# UniversalSaftSwitch.net
KiCad netlist of a schematic drawn in EAGLE
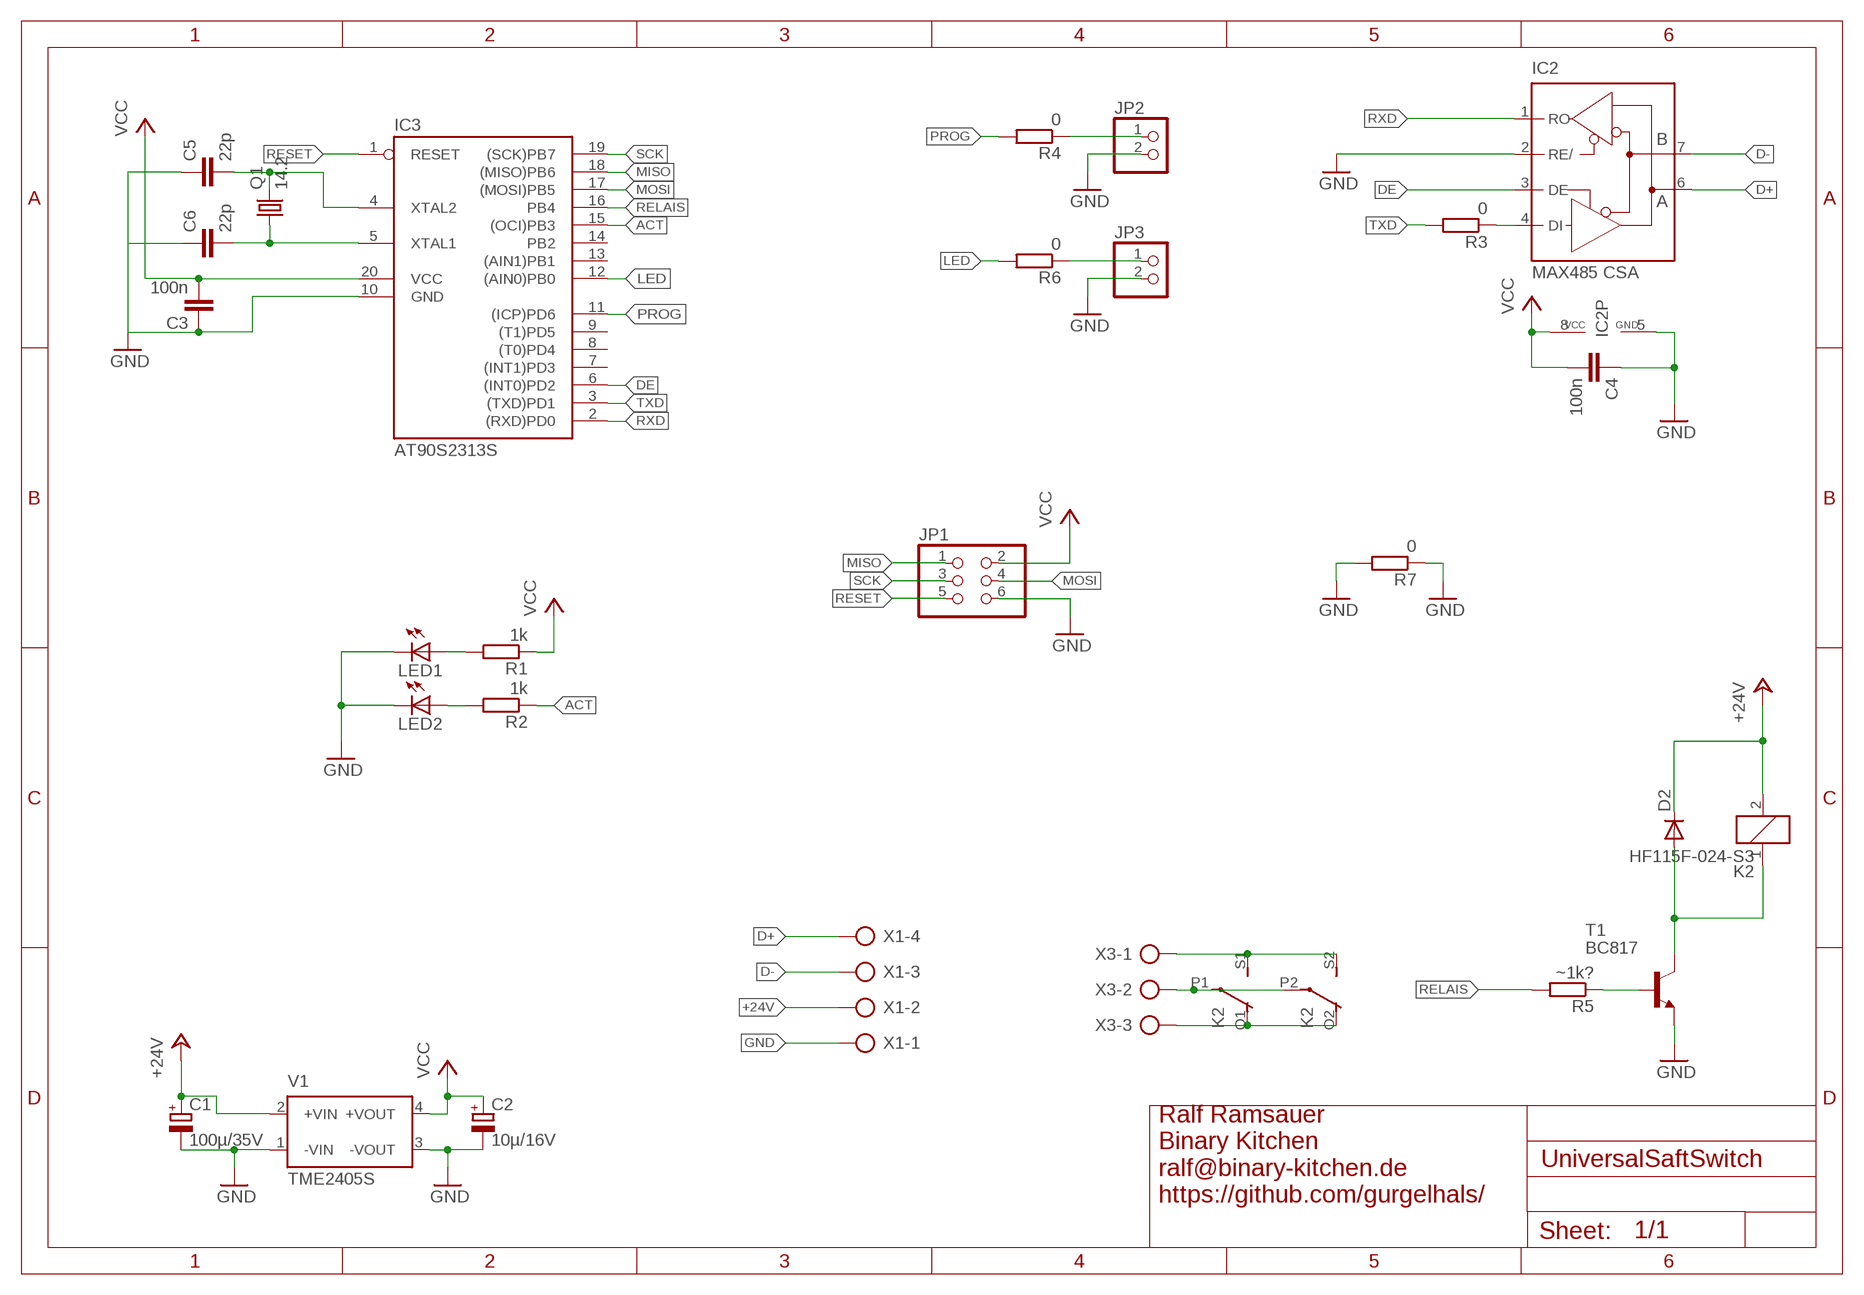
[diagram p0: schematic, sheet 1]

(export (version "E")
  (design (tool "Eeschema 10.0.6"))
  (components
    (comp (ref "C1")
      (value "100µ/35V")
      (footprint "eagle-import:E3,5-8")
      (libsource (lib "eagle-import") (part "CPOL-EUE3.5-8"))
    )
    (comp (ref "C2")
      (value "10µ/16V")
      (footprint "eagle-import:E2-4")
      (libsource (lib "eagle-import") (part "CPOL-EUE2-4"))
    )
    (comp (ref "C3")
      (value "100n")
      (footprint "eagle-import:C0805K")
      (libsource (lib "eagle-import") (part "C-EUC0805K"))
    )
    (comp (ref "C4")
      (value "100n")
      (footprint "eagle-import:C0805K")
      (libsource (lib "eagle-import") (part "C-EUC0805K"))
    )
    (comp (ref "C5")
      (value "22p")
      (footprint "eagle-import:C0805K")
      (libsource (lib "eagle-import") (part "C-EUC0805K"))
    )
    (comp (ref "C6")
      (value "22p")
      (footprint "eagle-import:C0805K")
      (libsource (lib "eagle-import") (part "C-EUC0805K"))
    )
    (comp (ref "D2")
      (value "DIODE-MINIMELF")
      (footprint "eagle-import:MINIMELF")
      (libsource (lib "eagle-import") (part "DIODE-MINIMELF"))
    )
    (comp (ref "IC2")
      (value "MAX485 CSA")
      (footprint "eagle-import:SO08")
      (libsource (lib "eagle-import") (part "MAX481CSA"))
    )
    (comp (ref "IC3")
      (value "AT90S2313S")
      (footprint "eagle-import:SO20L")
      (libsource (lib "eagle-import") (part "AT90S2313S"))
    )
    (comp (ref "JP1")
      (value "PINHD-2X3")
      (footprint "eagle-import:2X03")
      (libsource (lib "eagle-import") (part "PINHD-2X3"))
    )
    (comp (ref "JP2")
      (value "PINHD-1X2")
      (footprint "eagle-import:1X02")
      (libsource (lib "eagle-import") (part "PINHD-1X2"))
    )
    (comp (ref "JP3")
      (value "PINHD-1X2")
      (footprint "eagle-import:1X02")
      (libsource (lib "eagle-import") (part "PINHD-1X2"))
    )
    (comp (ref "K2")
      (value "HF115F-024-S3")
      (footprint "eagle-import:F4052")
      (libsource (lib "eagle-import") (part "4052"))
    )
    (comp (ref "LED1")
      (value "LED3MM")
      (footprint "eagle-import:LED3MM")
      (libsource (lib "eagle-import") (part "LED3MM"))
    )
    (comp (ref "LED2")
      (value "LED3MM")
      (footprint "eagle-import:LED3MM")
      (libsource (lib "eagle-import") (part "LED3MM"))
    )
    (comp (ref "Q1")
      (value "14.2")
      (footprint "eagle-import:HC49U-V")
      (libsource (lib "eagle-import") (part "CRYSTALHC49U-V"))
    )
    (comp (ref "R1")
      (value "1k")
      (footprint "eagle-import:M0805")
      (libsource (lib "eagle-import") (part "R-EU_M0805"))
    )
    (comp (ref "R2")
      (value "1k")
      (footprint "eagle-import:M0805")
      (libsource (lib "eagle-import") (part "R-EU_M0805"))
    )
    (comp (ref "R3")
      (value "0")
      (footprint "eagle-import:M0805")
      (libsource (lib "eagle-import") (part "R-EU_M0805"))
    )
    (comp (ref "R4")
      (value "0")
      (footprint "eagle-import:M0805")
      (libsource (lib "eagle-import") (part "R-EU_M0805"))
    )
    (comp (ref "R5")
      (value "~1k?")
      (footprint "eagle-import:M0805")
      (libsource (lib "eagle-import") (part "R-EU_M0805"))
    )
    (comp (ref "R6")
      (value "0")
      (footprint "eagle-import:M0805")
      (libsource (lib "eagle-import") (part "R-EU_M0805"))
    )
    (comp (ref "R7")
      (value "0")
      (footprint "eagle-import:M0805")
      (libsource (lib "eagle-import") (part "R-EU_M0805"))
    )
    (comp (ref "T1")
      (value "BC817")
      (footprint "eagle-import:SOT23-BEC")
      (libsource (lib "eagle-import") (part "-NPN-SOT23-BECBC817-16"))
    )
    (comp (ref "V1")
      (value "TME2405S")
      (footprint "eagle-import:TME-24V")
      (fields (field (name "MPN") "TME 2405S"))
      (libsource (lib "eagle-import") (part "TME?2405S"))
    )
    (comp (ref "X1")
      (value "AK500/4")
      (footprint "eagle-import:AK500_4")
      (libsource (lib "eagle-import") (part "AK500/4"))
    )
    (comp (ref "X3")
      (value "AK500/3")
      (footprint "eagle-import:AK500_3")
      (libsource (lib "eagle-import") (part "AK500/3"))
    )
  )
  (nets
    (net (code "1") (name "+24V") (class "Default")
      (node (ref "C1") (pin "+") (pinfunction "+_+") (pintype "passive"))
      (node (ref "D2") (pin "C") (pinfunction "C_C") (pintype "passive"))
      (node (ref "K2") (pin "2") (pinfunction "2_2") (pintype "passive"))
      (node (ref "V1") (pin "2") (pinfunction "+VIN_2") (pintype "passive"))
      (node (ref "X1") (pin "2") (pinfunction "KL_2") (pintype "passive"))
    )
    (net (code "2") (name "ACT") (class "Default")
      (node (ref "IC3") (pin "15") (pinfunction "(OCI)PB3_15") (pintype "bidirectional"))
      (node (ref "R2") (pin "1") (pinfunction "1_1") (pintype "passive"))
    )
    (net (code "3") (name "D+") (class "Default")
      (node (ref "IC2") (pin "6") (pinfunction "A_6") (pintype "passive"))
      (node (ref "X1") (pin "4") (pinfunction "KL_4") (pintype "passive"))
    )
    (net (code "4") (name "D-") (class "Default")
      (node (ref "IC2") (pin "7") (pinfunction "B_7") (pintype "passive"))
      (node (ref "X1") (pin "3") (pinfunction "KL_3") (pintype "passive"))
    )
    (net (code "5") (name "DE") (class "Default")
      (node (ref "IC2") (pin "3") (pinfunction "DE_3") (pintype "input"))
      (node (ref "IC3") (pin "6") (pinfunction "(INT0)PD2_6") (pintype "bidirectional"))
    )
    (net (code "6") (name "GND") (class "Default")
      (node (ref "C1") (pin "-") (pinfunction "-_-") (pintype "passive"))
      (node (ref "C2") (pin "-") (pinfunction "-_-") (pintype "passive"))
      (node (ref "C3") (pin "1") (pinfunction "1_1") (pintype "passive"))
      (node (ref "C4") (pin "1") (pinfunction "1_1") (pintype "passive"))
      (node (ref "C5") (pin "1") (pinfunction "1_1") (pintype "passive"))
      (node (ref "C6") (pin "1") (pinfunction "1_1") (pintype "passive"))
      (node (ref "IC2") (pin "2") (pinfunction "RE/_2") (pintype "input"))
      (node (ref "IC2") (pin "5") (pinfunction "GND_5") (pintype "power_in"))
      (node (ref "IC3") (pin "10") (pinfunction "GND_10") (pintype "power_in"))
      (node (ref "JP1") (pin "6") (pinfunction "6_6") (pintype "passive"))
      (node (ref "JP2") (pin "2") (pinfunction "2_2") (pintype "passive"))
      (node (ref "JP3") (pin "2") (pinfunction "2_2") (pintype "passive"))
      (node (ref "LED1") (pin "K") (pinfunction "C_K") (pintype "passive"))
      (node (ref "LED2") (pin "K") (pinfunction "C_K") (pintype "passive"))
      (node (ref "R7") (pin "1") (pinfunction "1_1") (pintype "passive"))
      (node (ref "R7") (pin "2") (pinfunction "2_2") (pintype "passive"))
      (node (ref "T1") (pin "E") (pinfunction "E_E") (pintype "passive"))
      (node (ref "V1") (pin "1") (pinfunction "-VIN_1") (pintype "passive"))
      (node (ref "V1") (pin "3") (pinfunction "-VOUT_3") (pintype "passive"))
      (node (ref "X1") (pin "1") (pinfunction "KL_1") (pintype "passive"))
    )
    (net (code "7") (name "LED") (class "Default")
      (node (ref "IC3") (pin "12") (pinfunction "(AIN0)PB0_12") (pintype "bidirectional"))
      (node (ref "R6") (pin "2") (pinfunction "2_2") (pintype "passive"))
    )
    (net (code "8") (name "MISO") (class "Default")
      (node (ref "IC3") (pin "18") (pinfunction "(MISO)PB6_18") (pintype "bidirectional"))
      (node (ref "JP1") (pin "1") (pinfunction "1_1") (pintype "passive"))
    )
    (net (code "9") (name "MOSI") (class "Default")
      (node (ref "IC3") (pin "17") (pinfunction "(MOSI)PB5_17") (pintype "bidirectional"))
      (node (ref "JP1") (pin "4") (pinfunction "4_4") (pintype "passive"))
    )
    (net (code "10") (name "Net-(D2-PadA)") (class "Default")
      (node (ref "D2") (pin "A") (pinfunction "A_A") (pintype "passive"))
      (node (ref "K2") (pin "1") (pinfunction "1_1") (pintype "passive"))
      (node (ref "T1") (pin "C") (pinfunction "C_C") (pintype "passive"))
    )
    (net (code "11") (name "Net-(IC2A-DI)") (class "Default")
      (node (ref "IC2") (pin "4") (pinfunction "DI_4") (pintype "input"))
      (node (ref "R3") (pin "1") (pinfunction "1_1") (pintype "passive"))
    )
    (net (code "12") (name "Net-(IC3-XTAL1)") (class "Default")
      (node (ref "C6") (pin "2") (pinfunction "2_2") (pintype "passive"))
      (node (ref "IC3") (pin "5") (pinfunction "XTAL1_5") (pintype "bidirectional"))
      (node (ref "Q1") (pin "1") (pinfunction "1_1") (pintype "passive"))
    )
    (net (code "13") (name "Net-(IC3-XTAL2)") (class "Default")
      (node (ref "C5") (pin "2") (pinfunction "2_2") (pintype "passive"))
      (node (ref "IC3") (pin "4") (pinfunction "XTAL2_4") (pintype "bidirectional"))
      (node (ref "Q1") (pin "2") (pinfunction "2_2") (pintype "passive"))
    )
    (net (code "14") (name "Net-(JP2-Pad1)") (class "Default")
      (node (ref "JP2") (pin "1") (pinfunction "1_1") (pintype "passive"))
      (node (ref "R4") (pin "1") (pinfunction "1_1") (pintype "passive"))
    )
    (net (code "15") (name "Net-(JP3-Pad1)") (class "Default")
      (node (ref "JP3") (pin "1") (pinfunction "1_1") (pintype "passive"))
      (node (ref "R6") (pin "1") (pinfunction "1_1") (pintype "passive"))
    )
    (net (code "16") (name "Net-(K2B-O)") (class "Default")
      (node (ref "K2") (pin "O1") (pinfunction "O_O1") (pintype "passive"))
      (node (ref "K2") (pin "O2") (pinfunction "O_O2") (pintype "passive"))
      (node (ref "X3") (pin "3") (pinfunction "KL_3") (pintype "passive"))
    )
    (net (code "17") (name "Net-(K2B-P)") (class "Default")
      (node (ref "K2") (pin "P1") (pinfunction "P_P1") (pintype "passive"))
      (node (ref "K2") (pin "P2") (pinfunction "P_P2") (pintype "passive"))
      (node (ref "X3") (pin "2") (pinfunction "KL_2") (pintype "passive"))
    )
    (net (code "18") (name "Net-(K2B-S)") (class "Default")
      (node (ref "K2") (pin "S1") (pinfunction "S_S1") (pintype "passive"))
      (node (ref "K2") (pin "S2") (pinfunction "S_S2") (pintype "passive"))
      (node (ref "X3") (pin "1") (pinfunction "KL_1") (pintype "passive"))
    )
    (net (code "19") (name "Net-(LED1-PadA)") (class "Default")
      (node (ref "LED1") (pin "A") (pinfunction "A_A") (pintype "passive"))
      (node (ref "R1") (pin "2") (pinfunction "2_2") (pintype "passive"))
    )
    (net (code "20") (name "Net-(LED2-PadA)") (class "Default")
      (node (ref "LED2") (pin "A") (pinfunction "A_A") (pintype "passive"))
      (node (ref "R2") (pin "2") (pinfunction "2_2") (pintype "passive"))
    )
    (net (code "21") (name "Net-(R5-Pad1)") (class "Default")
      (node (ref "R5") (pin "1") (pinfunction "1_1") (pintype "passive"))
      (node (ref "T1") (pin "B") (pinfunction "B_B") (pintype "passive"))
    )
    (net (code "22") (name "PROG") (class "Default")
      (node (ref "IC3") (pin "11") (pinfunction "(ICP)PD6_11") (pintype "bidirectional"))
      (node (ref "R4") (pin "2") (pinfunction "2_2") (pintype "passive"))
    )
    (net (code "23") (name "RELAIS") (class "Default")
      (node (ref "IC3") (pin "16") (pinfunction "PB4_16") (pintype "bidirectional"))
      (node (ref "R5") (pin "2") (pinfunction "2_2") (pintype "passive"))
    )
    (net (code "24") (name "RESET") (class "Default")
      (node (ref "IC3") (pin "1") (pinfunction "RESET_1") (pintype "bidirectional"))
      (node (ref "JP1") (pin "5") (pinfunction "5_5") (pintype "passive"))
    )
    (net (code "25") (name "RXD") (class "Default")
      (node (ref "IC2") (pin "1") (pinfunction "RO_1") (pintype "output"))
      (node (ref "IC3") (pin "2") (pinfunction "(RXD)PD0_2") (pintype "bidirectional"))
    )
    (net (code "26") (name "SCK") (class "Default")
      (node (ref "IC3") (pin "19") (pinfunction "(SCK)PB7_19") (pintype "bidirectional"))
      (node (ref "JP1") (pin "3") (pinfunction "3_3") (pintype "passive"))
    )
    (net (code "27") (name "TXD") (class "Default")
      (node (ref "IC3") (pin "3") (pinfunction "(TXD)PD1_3") (pintype "bidirectional"))
      (node (ref "R3") (pin "2") (pinfunction "2_2") (pintype "passive"))
    )
    (net (code "28") (name "VCC") (class "Default")
      (node (ref "C2") (pin "+") (pinfunction "+_+") (pintype "passive"))
      (node (ref "C3") (pin "2") (pinfunction "2_2") (pintype "passive"))
      (node (ref "C4") (pin "2") (pinfunction "2_2") (pintype "passive"))
      (node (ref "IC2") (pin "8") (pinfunction "VCC_8") (pintype "power_in"))
      (node (ref "IC3") (pin "20") (pinfunction "VCC_20") (pintype "power_in"))
      (node (ref "JP1") (pin "2") (pinfunction "2_2") (pintype "passive"))
      (node (ref "R1") (pin "1") (pinfunction "1_1") (pintype "passive"))
      (node (ref "V1") (pin "4") (pinfunction "+VOUT_4") (pintype "passive"))
    )
    (net (code "29") (name "unconnected-(IC3-(AIN1)PB1-Pad13)") (class "Default")
      (node (ref "IC3") (pin "13") (pinfunction "(AIN1)PB1_13") (pintype "bidirectional"))
    )
    (net (code "30") (name "unconnected-(IC3-(INT1)PD3-Pad7)") (class "Default")
      (node (ref "IC3") (pin "7") (pinfunction "(INT1)PD3_7") (pintype "bidirectional"))
    )
    (net (code "31") (name "unconnected-(IC3-(T0)PD4-Pad8)") (class "Default")
      (node (ref "IC3") (pin "8") (pinfunction "(T0)PD4_8") (pintype "bidirectional"))
    )
    (net (code "32") (name "unconnected-(IC3-(T1)PD5-Pad9)") (class "Default")
      (node (ref "IC3") (pin "9") (pinfunction "(T1)PD5_9") (pintype "bidirectional"))
    )
    (net (code "33") (name "unconnected-(IC3-PB2-Pad14)") (class "Default")
      (node (ref "IC3") (pin "14") (pinfunction "PB2_14") (pintype "bidirectional"))
    )
  )
)
